# mainboard.net
KiCad netlist of a schematic drawn in EAGLE
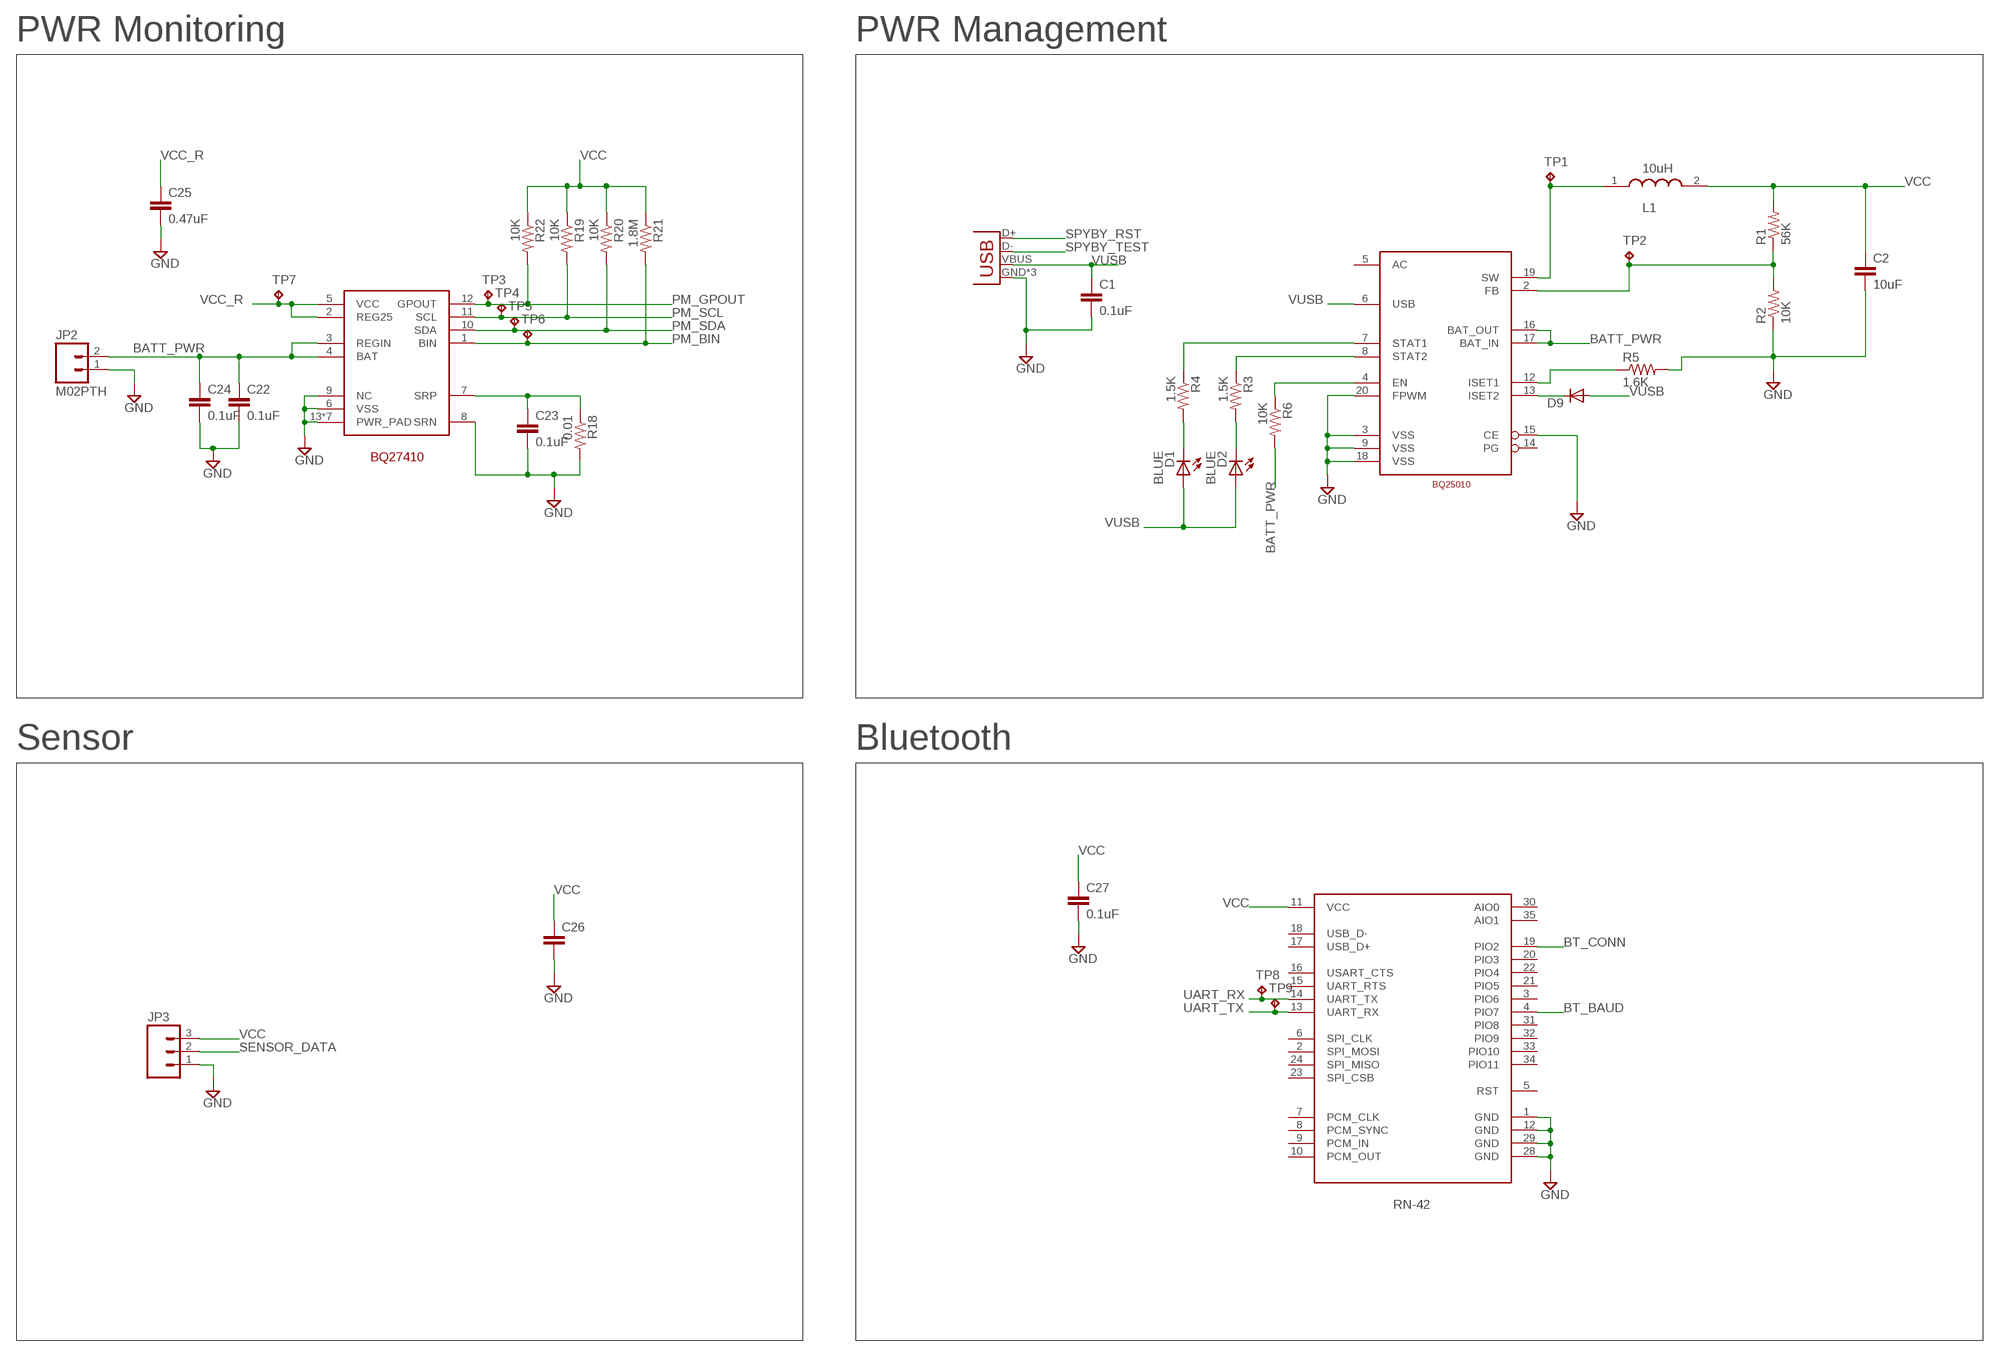
[diagram p0: schematic, sheet 1, part 1 of 2]
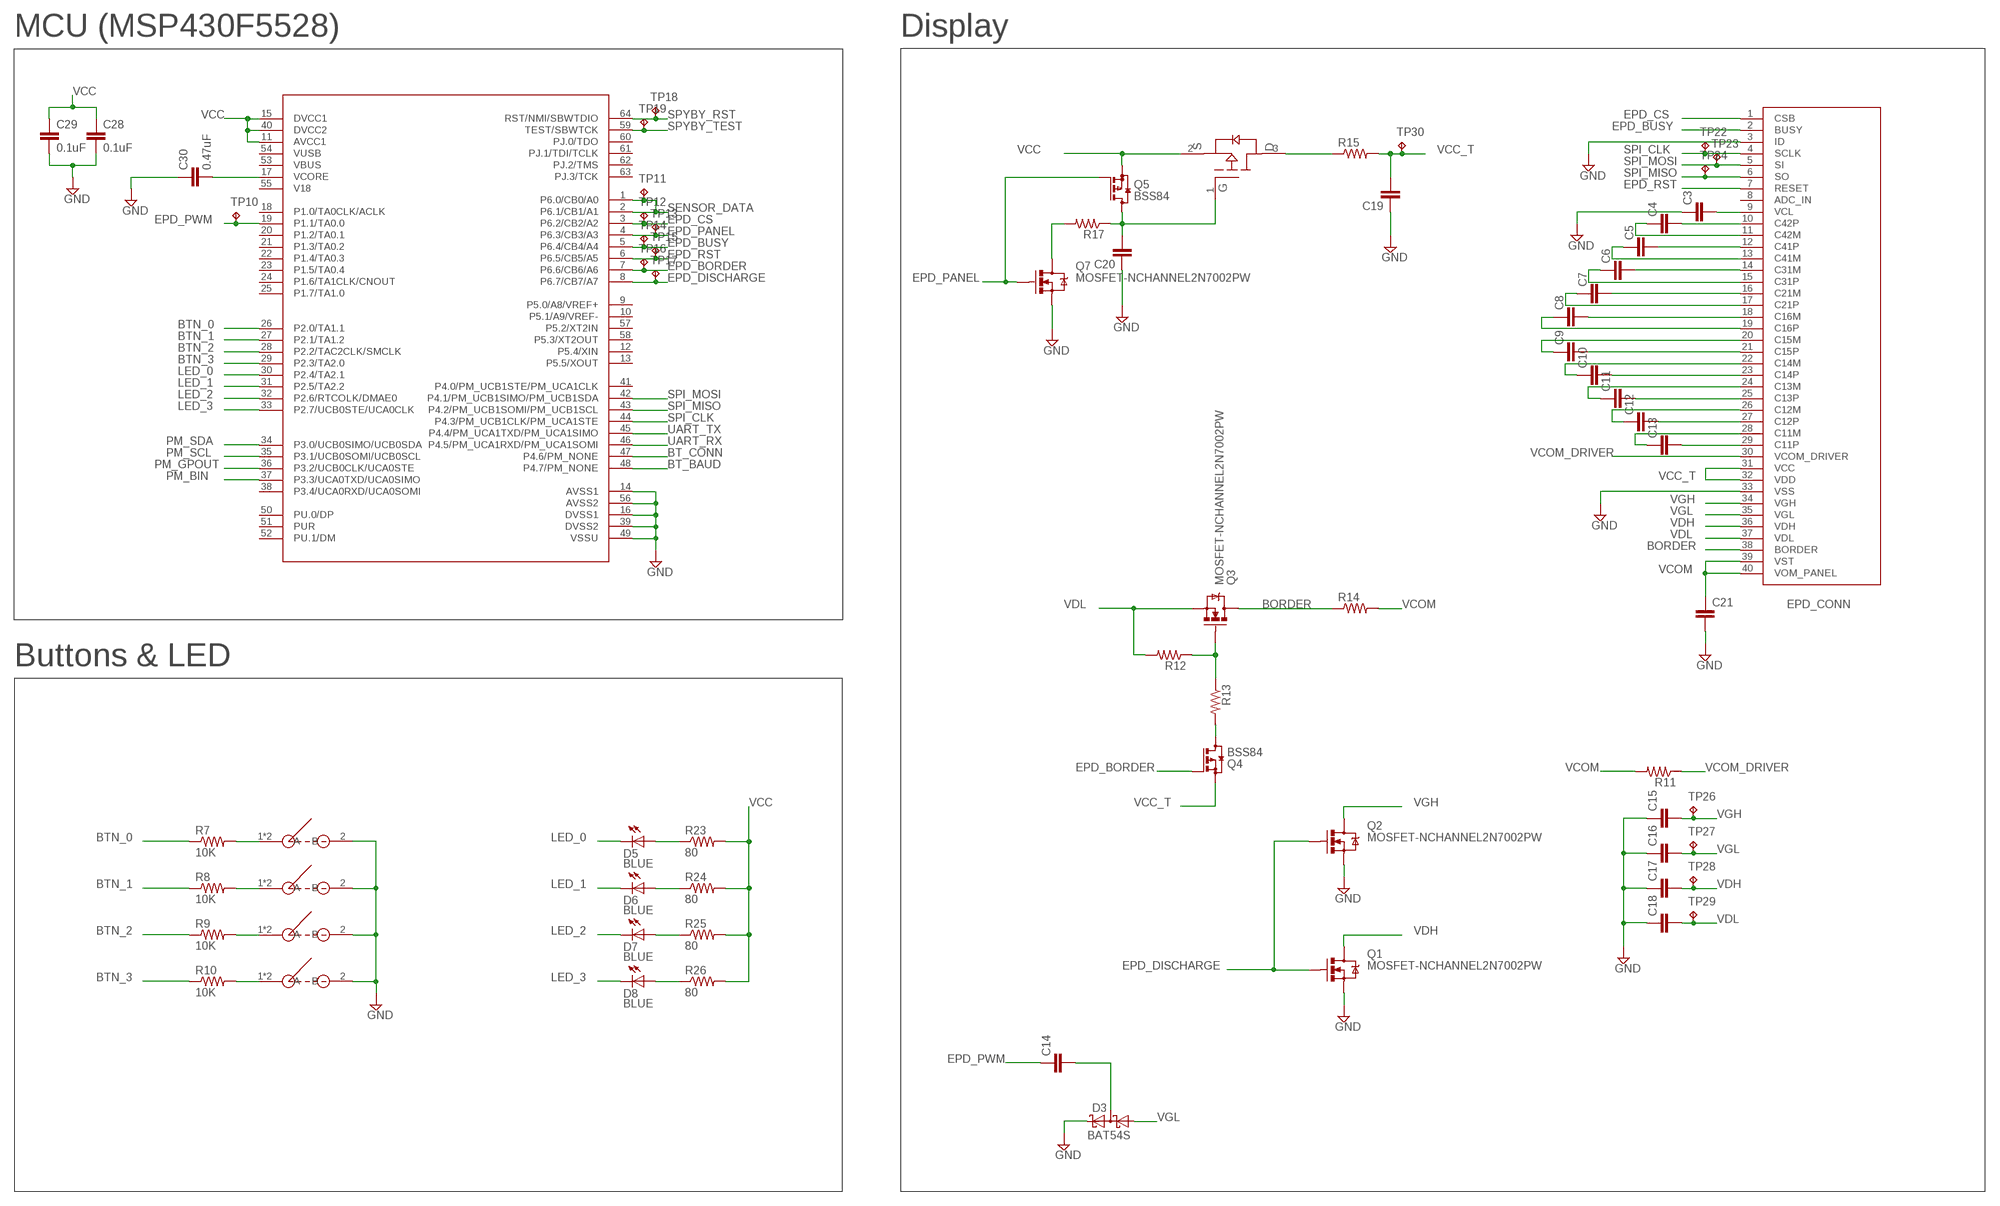
[diagram p1: schematic, sheet 1, part 2 of 2]

(export (version "E")
  (design (tool "Eeschema 10.0.6"))
  (components
    (comp (ref "C1")
      (value "0.1uF")
      (footprint "eagle-import:0402-CAP")
      (libsource (lib "eagle-import") (part "CAP0402-CAP"))
    )
    (comp (ref "C2")
      (value "10uF")
      (footprint "eagle-import:0402-CAP")
      (libsource (lib "eagle-import") (part "CAP0402-CAP"))
    )
    (comp (ref "C3")
      (value "CAP0402-CAP")
      (footprint "eagle-import:0402-CAP")
      (libsource (lib "eagle-import") (part "CAP0402-CAP"))
    )
    (comp (ref "C4")
      (value "CAP0402-CAP")
      (footprint "eagle-import:0402-CAP")
      (libsource (lib "eagle-import") (part "CAP0402-CAP"))
    )
    (comp (ref "C5")
      (value "CAP0402-CAP")
      (footprint "eagle-import:0402-CAP")
      (libsource (lib "eagle-import") (part "CAP0402-CAP"))
    )
    (comp (ref "C6")
      (value "CAP0402-CAP")
      (footprint "eagle-import:0402-CAP")
      (libsource (lib "eagle-import") (part "CAP0402-CAP"))
    )
    (comp (ref "C7")
      (value "CAP0402-CAP")
      (footprint "eagle-import:0402-CAP")
      (libsource (lib "eagle-import") (part "CAP0402-CAP"))
    )
    (comp (ref "C8")
      (value "CAP0402-CAP")
      (footprint "eagle-import:0402-CAP")
      (libsource (lib "eagle-import") (part "CAP0402-CAP"))
    )
    (comp (ref "C9")
      (value "CAP0402-CAP")
      (footprint "eagle-import:0402-CAP")
      (libsource (lib "eagle-import") (part "CAP0402-CAP"))
    )
    (comp (ref "C10")
      (value "CAP0402-CAP")
      (footprint "eagle-import:0402-CAP")
      (libsource (lib "eagle-import") (part "CAP0402-CAP"))
    )
    (comp (ref "C11")
      (value "CAP0402-CAP")
      (footprint "eagle-import:0402-CAP")
      (libsource (lib "eagle-import") (part "CAP0402-CAP"))
    )
    (comp (ref "C12")
      (value "CAP0402-CAP")
      (footprint "eagle-import:0402-CAP")
      (libsource (lib "eagle-import") (part "CAP0402-CAP"))
    )
    (comp (ref "C13")
      (value "CAP0402-CAP")
      (footprint "eagle-import:0402-CAP")
      (libsource (lib "eagle-import") (part "CAP0402-CAP"))
    )
    (comp (ref "C14")
      (value "CAP0402-CAP")
      (footprint "eagle-import:0402-CAP")
      (libsource (lib "eagle-import") (part "CAP0402-CAP"))
    )
    (comp (ref "C15")
      (value "CAP0402-CAP")
      (footprint "eagle-import:0402-CAP")
      (libsource (lib "eagle-import") (part "CAP0402-CAP"))
    )
    (comp (ref "C16")
      (value "CAP0402-CAP")
      (footprint "eagle-import:0402-CAP")
      (libsource (lib "eagle-import") (part "CAP0402-CAP"))
    )
    (comp (ref "C17")
      (value "CAP0402-CAP")
      (footprint "eagle-import:0402-CAP")
      (libsource (lib "eagle-import") (part "CAP0402-CAP"))
    )
    (comp (ref "C18")
      (value "CAP0402-CAP")
      (footprint "eagle-import:0402-CAP")
      (libsource (lib "eagle-import") (part "CAP0402-CAP"))
    )
    (comp (ref "C19")
      (value "CAP0402-CAP")
      (footprint "eagle-import:0402-CAP")
      (libsource (lib "eagle-import") (part "CAP0402-CAP"))
    )
    (comp (ref "C20")
      (value "CAP0402-CAP")
      (footprint "eagle-import:0402-CAP")
      (libsource (lib "eagle-import") (part "CAP0402-CAP"))
    )
    (comp (ref "C21")
      (value "CAP0402-CAP")
      (footprint "eagle-import:0402-CAP")
      (libsource (lib "eagle-import") (part "CAP0402-CAP"))
    )
    (comp (ref "C22")
      (value "0.1uF")
      (footprint "eagle-import:0402-CAP")
      (libsource (lib "eagle-import") (part "CAP0402-CAP"))
    )
    (comp (ref "C23")
      (value "0.1uF")
      (footprint "eagle-import:0402-CAP")
      (libsource (lib "eagle-import") (part "CAP0402-CAP"))
    )
    (comp (ref "C24")
      (value "0.1uF")
      (footprint "eagle-import:0402-CAP")
      (libsource (lib "eagle-import") (part "CAP0402-CAP"))
    )
    (comp (ref "C25")
      (value "0.47uF")
      (footprint "eagle-import:0402-CAP")
      (libsource (lib "eagle-import") (part "CAP0402-CAP"))
    )
    (comp (ref "C26")
      (value "CAP0402-CAP")
      (footprint "eagle-import:0402-CAP")
      (libsource (lib "eagle-import") (part "CAP0402-CAP"))
    )
    (comp (ref "C27")
      (value "0.1uF")
      (footprint "eagle-import:0402-CAP")
      (libsource (lib "eagle-import") (part "CAP0402-CAP"))
    )
    (comp (ref "C28")
      (value "0.1uF")
      (footprint "eagle-import:0402-CAP")
      (libsource (lib "eagle-import") (part "CAP0402-CAP"))
    )
    (comp (ref "C29")
      (value "0.1uF")
      (footprint "eagle-import:0402-CAP")
      (libsource (lib "eagle-import") (part "CAP0402-CAP"))
    )
    (comp (ref "C30")
      (value "0.47uF")
      (footprint "eagle-import:0402-CAP")
      (libsource (lib "eagle-import") (part "CAP0402-CAP"))
    )
    (comp (ref "D1")
      (value "BLUE")
      (footprint "eagle-import:LED-0603")
      (libsource (lib "eagle-import") (part "LED-BLUE0603"))
    )
    (comp (ref "D2")
      (value "BLUE")
      (footprint "eagle-import:LED-0603")
      (libsource (lib "eagle-import") (part "LED-BLUE0603"))
    )
    (comp (ref "D3")
      (value "BAT54S")
      (footprint "eagle-import:SOT23")
      (libsource (lib "eagle-import") (part "BAT54S"))
    )
    (comp (ref "D5")
      (value "BLUE")
      (footprint "eagle-import:LED-0603")
      (libsource (lib "eagle-import") (part "LED-BLUE0603"))
    )
    (comp (ref "D6")
      (value "BLUE")
      (footprint "eagle-import:LED-0603")
      (libsource (lib "eagle-import") (part "LED-BLUE0603"))
    )
    (comp (ref "D7")
      (value "BLUE")
      (footprint "eagle-import:LED-0603")
      (libsource (lib "eagle-import") (part "LED-BLUE0603"))
    )
    (comp (ref "D8")
      (value "BLUE")
      (footprint "eagle-import:LED-0603")
      (libsource (lib "eagle-import") (part "LED-BLUE0603"))
    )
    (comp (ref "D9")
      (value "DIODESOD523")
      (footprint "eagle-import:SOD523")
      (libsource (lib "eagle-import") (part "DIODESOD523"))
    )
    (comp (ref "JP1")
      (value "USB-MICROB")
      (footprint "eagle-import:USB-MICROB")
      (libsource (lib "eagle-import") (part "USB-MICROB"))
    )
    (comp (ref "JP2")
      (value "M02PTH")
      (footprint "eagle-import:1X02")
      (libsource (lib "eagle-import") (part "M02PTH"))
    )
    (comp (ref "JP3")
      (value "M03PTH")
      (footprint "eagle-import:1X03")
      (libsource (lib "eagle-import") (part "M03PTH"))
    )
    (comp (ref "L1")
      (value "10uH")
      (footprint "eagle-import:ASPI_0428S-100M-T")
      (libsource (lib "eagle-import") (part "ASPI-0428S-100M-T"))
    )
    (comp (ref "Q1")
      (value "MOSFET-NCHANNEL2N7002PW")
      (footprint "eagle-import:SOT323")
      (libsource (lib "eagle-import") (part "MOSFET-NCHANNEL2N7002PW"))
    )
    (comp (ref "Q2")
      (value "MOSFET-NCHANNEL2N7002PW")
      (footprint "eagle-import:SOT323")
      (libsource (lib "eagle-import") (part "MOSFET-NCHANNEL2N7002PW"))
    )
    (comp (ref "Q3")
      (value "MOSFET-NCHANNEL2N7002PW")
      (footprint "eagle-import:SOT323")
      (libsource (lib "eagle-import") (part "MOSFET-NCHANNEL2N7002PW"))
    )
    (comp (ref "Q4")
      (value "BSS84")
      (footprint "eagle-import:SOT23")
      (libsource (lib "eagle-import") (part "BSS84"))
    )
    (comp (ref "Q5")
      (value "BSS84")
      (footprint "eagle-import:SOT23")
      (libsource (lib "eagle-import") (part "BSS84"))
    )
    (comp (ref "Q7")
      (value "MOSFET-NCHANNEL2N7002PW")
      (footprint "eagle-import:SOT323")
      (libsource (lib "eagle-import") (part "MOSFET-NCHANNEL2N7002PW"))
    )
    (comp (ref "R1")
      (value "56K")
      (footprint "eagle-import:0402-RES")
      (libsource (lib "eagle-import") (part "RESISTOR0402-RES"))
    )
    (comp (ref "R2")
      (value "10K")
      (footprint "eagle-import:0402-RES")
      (libsource (lib "eagle-import") (part "RESISTOR0402-RES"))
    )
    (comp (ref "R3")
      (value "1.5K")
      (footprint "eagle-import:0402-RES")
      (libsource (lib "eagle-import") (part "RESISTOR0402-RES"))
    )
    (comp (ref "R4")
      (value "1.5K")
      (footprint "eagle-import:0402-RES")
      (libsource (lib "eagle-import") (part "RESISTOR0402-RES"))
    )
    (comp (ref "R5")
      (value "1.6K")
      (footprint "eagle-import:0402-RES")
      (libsource (lib "eagle-import") (part "RESISTOR0402-RES"))
    )
    (comp (ref "R6")
      (value "10K")
      (footprint "eagle-import:0402-RES")
      (libsource (lib "eagle-import") (part "RESISTOR0402-RES"))
    )
    (comp (ref "R7")
      (value "10K")
      (footprint "eagle-import:0402-RES")
      (libsource (lib "eagle-import") (part "RESISTOR0402-RES"))
    )
    (comp (ref "R8")
      (value "10K")
      (footprint "eagle-import:0402-RES")
      (libsource (lib "eagle-import") (part "RESISTOR0402-RES"))
    )
    (comp (ref "R9")
      (value "10K")
      (footprint "eagle-import:0402-RES")
      (libsource (lib "eagle-import") (part "RESISTOR0402-RES"))
    )
    (comp (ref "R10")
      (value "10K")
      (footprint "eagle-import:0402-RES")
      (libsource (lib "eagle-import") (part "RESISTOR0402-RES"))
    )
    (comp (ref "R11")
      (value "RESISTOR0402-RES")
      (footprint "eagle-import:0402-RES")
      (libsource (lib "eagle-import") (part "RESISTOR0402-RES"))
    )
    (comp (ref "R12")
      (value "RESISTOR0402-RES")
      (footprint "eagle-import:0402-RES")
      (libsource (lib "eagle-import") (part "RESISTOR0402-RES"))
    )
    (comp (ref "R13")
      (value "RESISTOR0402-RES")
      (footprint "eagle-import:0402-RES")
      (libsource (lib "eagle-import") (part "RESISTOR0402-RES"))
    )
    (comp (ref "R14")
      (value "RESISTOR0402-RES")
      (footprint "eagle-import:0402-RES")
      (libsource (lib "eagle-import") (part "RESISTOR0402-RES"))
    )
    (comp (ref "R15")
      (value "RESISTOR0402-RES")
      (footprint "eagle-import:0402-RES")
      (libsource (lib "eagle-import") (part "RESISTOR0402-RES"))
    )
    (comp (ref "R17")
      (value "RESISTOR0402-RES")
      (footprint "eagle-import:0402-RES")
      (libsource (lib "eagle-import") (part "RESISTOR0402-RES"))
    )
    (comp (ref "R18")
      (value "0.01")
      (footprint "eagle-import:0402-RES")
      (libsource (lib "eagle-import") (part "RESISTOR0402-RES"))
    )
    (comp (ref "R19")
      (value "10K")
      (footprint "eagle-import:0402-RES")
      (libsource (lib "eagle-import") (part "RESISTOR0402-RES"))
    )
    (comp (ref "R20")
      (value "10K")
      (footprint "eagle-import:0402-RES")
      (libsource (lib "eagle-import") (part "RESISTOR0402-RES"))
    )
    (comp (ref "R21")
      (value "1.8M")
      (footprint "eagle-import:0402-RES")
      (libsource (lib "eagle-import") (part "RESISTOR0402-RES"))
    )
    (comp (ref "R22")
      (value "10K")
      (footprint "eagle-import:0402-RES")
      (libsource (lib "eagle-import") (part "RESISTOR0402-RES"))
    )
    (comp (ref "R23")
      (value "80")
      (footprint "eagle-import:0402-RES")
      (libsource (lib "eagle-import") (part "RESISTOR0402-RES"))
    )
    (comp (ref "R24")
      (value "80")
      (footprint "eagle-import:0402-RES")
      (libsource (lib "eagle-import") (part "RESISTOR0402-RES"))
    )
    (comp (ref "R25")
      (value "80")
      (footprint "eagle-import:0402-RES")
      (libsource (lib "eagle-import") (part "RESISTOR0402-RES"))
    )
    (comp (ref "R26")
      (value "80")
      (footprint "eagle-import:0402-RES")
      (libsource (lib "eagle-import") (part "RESISTOR0402-RES"))
    )
    (comp (ref "TP1")
      (value "TPB1,27")
      (footprint "eagle-import:B1,27")
      (libsource (lib "eagle-import") (part "TPB1,27"))
    )
    (comp (ref "TP2")
      (value "TPB1,27")
      (footprint "eagle-import:B1,27")
      (libsource (lib "eagle-import") (part "TPB1,27"))
    )
    (comp (ref "TP3")
      (value "TPB1,27")
      (footprint "eagle-import:B1,27")
      (libsource (lib "eagle-import") (part "TPB1,27"))
    )
    (comp (ref "TP4")
      (value "TPB1,27")
      (footprint "eagle-import:B1,27")
      (libsource (lib "eagle-import") (part "TPB1,27"))
    )
    (comp (ref "TP5")
      (value "TPB1,27")
      (footprint "eagle-import:B1,27")
      (libsource (lib "eagle-import") (part "TPB1,27"))
    )
    (comp (ref "TP6")
      (value "TPB1,27")
      (footprint "eagle-import:B1,27")
      (libsource (lib "eagle-import") (part "TPB1,27"))
    )
    (comp (ref "TP7")
      (value "TPB1,27")
      (footprint "eagle-import:B1,27")
      (libsource (lib "eagle-import") (part "TPB1,27"))
    )
    (comp (ref "TP8")
      (value "TPB1,27")
      (footprint "eagle-import:B1,27")
      (libsource (lib "eagle-import") (part "TPB1,27"))
    )
    (comp (ref "TP9")
      (value "TPB1,27")
      (footprint "eagle-import:B1,27")
      (libsource (lib "eagle-import") (part "TPB1,27"))
    )
    (comp (ref "TP10")
      (value "TPB1,27")
      (footprint "eagle-import:B1,27")
      (libsource (lib "eagle-import") (part "TPB1,27"))
    )
    (comp (ref "TP11")
      (value "TPB1,27")
      (footprint "eagle-import:B1,27")
      (libsource (lib "eagle-import") (part "TPB1,27"))
    )
    (comp (ref "TP12")
      (value "TPB1,27")
      (footprint "eagle-import:B1,27")
      (libsource (lib "eagle-import") (part "TPB1,27"))
    )
    (comp (ref "TP13")
      (value "TPB1,27")
      (footprint "eagle-import:B1,27")
      (libsource (lib "eagle-import") (part "TPB1,27"))
    )
    (comp (ref "TP14")
      (value "TPB1,27")
      (footprint "eagle-import:B1,27")
      (libsource (lib "eagle-import") (part "TPB1,27"))
    )
    (comp (ref "TP15")
      (value "TPB1,27")
      (footprint "eagle-import:B1,27")
      (libsource (lib "eagle-import") (part "TPB1,27"))
    )
    (comp (ref "TP16")
      (value "TPB1,27")
      (footprint "eagle-import:B1,27")
      (libsource (lib "eagle-import") (part "TPB1,27"))
    )
    (comp (ref "TP17")
      (value "TPB1,27")
      (footprint "eagle-import:B1,27")
      (libsource (lib "eagle-import") (part "TPB1,27"))
    )
    (comp (ref "TP18")
      (value "TPB1,27")
      (footprint "eagle-import:B1,27")
      (libsource (lib "eagle-import") (part "TPB1,27"))
    )
    (comp (ref "TP19")
      (value "TPB1,27")
      (footprint "eagle-import:B1,27")
      (libsource (lib "eagle-import") (part "TPB1,27"))
    )
    (comp (ref "TP22")
      (value "TPB1,27")
      (footprint "eagle-import:B1,27")
      (libsource (lib "eagle-import") (part "TPB1,27"))
    )
    (comp (ref "TP23")
      (value "TPB1,27")
      (footprint "eagle-import:B1,27")
      (libsource (lib "eagle-import") (part "TPB1,27"))
    )
    (comp (ref "TP24")
      (value "TPB1,27")
      (footprint "eagle-import:B1,27")
      (libsource (lib "eagle-import") (part "TPB1,27"))
    )
    (comp (ref "TP26")
      (value "TPB1,27")
      (footprint "eagle-import:B1,27")
      (libsource (lib "eagle-import") (part "TPB1,27"))
    )
    (comp (ref "TP27")
      (value "TPB1,27")
      (footprint "eagle-import:B1,27")
      (libsource (lib "eagle-import") (part "TPB1,27"))
    )
    (comp (ref "TP28")
      (value "TPB1,27")
      (footprint "eagle-import:B1,27")
      (libsource (lib "eagle-import") (part "TPB1,27"))
    )
    (comp (ref "TP29")
      (value "TPB1,27")
      (footprint "eagle-import:B1,27")
      (libsource (lib "eagle-import") (part "TPB1,27"))
    )
    (comp (ref "TP30")
      (value "TPB1,27")
      (footprint "eagle-import:B1,27")
      (libsource (lib "eagle-import") (part "TPB1,27"))
    )
    (comp (ref "U$1")
      (value "MSP430F5528")
      (footprint "eagle-import:VQFN_RGC_64PIN")
      (libsource (lib "eagle-import") (part "MSP430F5528"))
    )
    (comp (ref "U$2")
      (value "RN-42")
      (footprint "eagle-import:RN-42")
      (libsource (lib "eagle-import") (part "RN-42"))
    )
    (comp (ref "U$3")
      (value "BQ25010")
      (footprint "eagle-import:VQFN_RHL_20PIN")
      (libsource (lib "eagle-import") (part "BQ25010"))
    )
    (comp (ref "U$4")
      (value "EVP-AEDB2A")
      (footprint "eagle-import:EVP-AEDB2A")
      (libsource (lib "eagle-import") (part "EVP-AEDB2A"))
    )
    (comp (ref "U$5")
      (value "EVP-AEDB2A")
      (footprint "eagle-import:EVP-AEDB2A")
      (libsource (lib "eagle-import") (part "EVP-AEDB2A"))
    )
    (comp (ref "U$6")
      (value "EVP-AEDB2A")
      (footprint "eagle-import:EVP-AEDB2A")
      (libsource (lib "eagle-import") (part "EVP-AEDB2A"))
    )
    (comp (ref "U$7")
      (value "EVP-AEDB2A")
      (footprint "eagle-import:EVP-AEDB2A")
      (libsource (lib "eagle-import") (part "EVP-AEDB2A"))
    )
    (comp (ref "U$8")
      (value "FH12-40S-0.5SH")
      (footprint "eagle-import:FH12-40S-0.5SH")
      (libsource (lib "eagle-import") (part "FH12-40S-0.5SH"))
    )
    (comp (ref "U$9")
      (value "BQ27410")
      (footprint "eagle-import:SON_DRZ_12PIN")
      (libsource (lib "eagle-import") (part "BQ27410"))
    )
    (comp (ref "U$10")
      (value "DMG2305UX")
      (footprint "eagle-import:SOT23")
      (libsource (lib "eagle-import") (part "DMG2305UX"))
    )
  )
  (nets
    (net (code "1") (name "/BATT_PWR") (class "Default")
      (node (ref "C22") (pin "1") (pinfunction "1_1") (pintype "passive"))
      (node (ref "C24") (pin "1") (pinfunction "1_1") (pintype "passive"))
      (node (ref "JP2") (pin "2") (pinfunction "2_2") (pintype "passive"))
      (node (ref "R6") (pin "2") (pinfunction "2_2") (pintype "passive"))
      (node (ref "U$3") (pin "16") (pinfunction "BAT_OUT_16") (pintype "bidirectional"))
      (node (ref "U$3") (pin "17") (pinfunction "BAT_IN_17") (pintype "bidirectional"))
      (node (ref "U$9") (pin "3") (pinfunction "REGIN_3") (pintype "bidirectional"))
      (node (ref "U$9") (pin "4") (pinfunction "BAT_4") (pintype "bidirectional"))
    )
    (net (code "2") (name "/BORDER") (class "Default")
      (node (ref "Q3") (pin "3") (pinfunction "D_3") (pintype "passive"))
      (node (ref "R14") (pin "1") (pinfunction "1_1") (pintype "passive"))
      (node (ref "U$8") (pin "38") (pinfunction "BORDER_38") (pintype "bidirectional"))
    )
    (net (code "3") (name "/BTN_0") (class "Default")
      (node (ref "R7") (pin "1") (pinfunction "1_1") (pintype "passive"))
      (node (ref "U$1") (pin "26") (pinfunction "P2.0/TA1.1_26") (pintype "bidirectional"))
    )
    (net (code "4") (name "/BTN_1") (class "Default")
      (node (ref "R8") (pin "1") (pinfunction "1_1") (pintype "passive"))
      (node (ref "U$1") (pin "27") (pinfunction "P2.1/TA1.2_27") (pintype "bidirectional"))
    )
    (net (code "5") (name "/BTN_2") (class "Default")
      (node (ref "R9") (pin "1") (pinfunction "1_1") (pintype "passive"))
      (node (ref "U$1") (pin "28") (pinfunction "P2.2/TAC2CLK/SMCLK_28") (pintype "bidirectional"))
    )
    (net (code "6") (name "/BTN_3") (class "Default")
      (node (ref "R10") (pin "1") (pinfunction "1_1") (pintype "passive"))
      (node (ref "U$1") (pin "29") (pinfunction "P2.3/TA2.0_29") (pintype "bidirectional"))
    )
    (net (code "7") (name "/BT_BAUD") (class "Default")
      (node (ref "U$1") (pin "48") (pinfunction "P4.7/PM_NONE_48") (pintype "bidirectional"))
      (node (ref "U$2") (pin "4") (pinfunction "PIO7_4") (pintype "bidirectional"))
    )
    (net (code "8") (name "/BT_CONN") (class "Default")
      (node (ref "U$1") (pin "47") (pinfunction "P4.6/PM_NONE_47") (pintype "bidirectional"))
      (node (ref "U$2") (pin "19") (pinfunction "PIO2_19") (pintype "bidirectional"))
    )
    (net (code "9") (name "/EPD_BORDER") (class "Default")
      (node (ref "Q4") (pin "1") (pinfunction "G_1") (pintype "passive"))
      (node (ref "TP16") (pin "TP") (pinfunction "TP_TP") (pintype "input"))
      (node (ref "U$1") (pin "7") (pinfunction "P6.6/CB6/A6_7") (pintype "bidirectional"))
    )
    (net (code "10") (name "/EPD_BUSY") (class "Default")
      (node (ref "TP14") (pin "TP") (pinfunction "TP_TP") (pintype "input"))
      (node (ref "U$1") (pin "5") (pinfunction "P6.4/CB4/A4_5") (pintype "bidirectional"))
      (node (ref "U$8") (pin "2") (pinfunction "BUSY_2") (pintype "bidirectional"))
    )
    (net (code "11") (name "/EPD_CS") (class "Default")
      (node (ref "TP12") (pin "TP") (pinfunction "TP_TP") (pintype "input"))
      (node (ref "U$1") (pin "3") (pinfunction "P6.2/CB2/A2_3") (pintype "bidirectional"))
      (node (ref "U$8") (pin "1") (pinfunction "CSB_1") (pintype "bidirectional"))
    )
    (net (code "12") (name "/EPD_DISCHARGE") (class "Default")
      (node (ref "Q1") (pin "1") (pinfunction "G_1") (pintype "passive"))
      (node (ref "Q2") (pin "1") (pinfunction "G_1") (pintype "passive"))
      (node (ref "TP17") (pin "TP") (pinfunction "TP_TP") (pintype "input"))
      (node (ref "U$1") (pin "8") (pinfunction "P6.7/CB7/A7_8") (pintype "bidirectional"))
    )
    (net (code "13") (name "/EPD_PANEL") (class "Default")
      (node (ref "Q5") (pin "1") (pinfunction "G_1") (pintype "passive"))
      (node (ref "Q7") (pin "1") (pinfunction "G_1") (pintype "passive"))
      (node (ref "TP13") (pin "TP") (pinfunction "TP_TP") (pintype "input"))
      (node (ref "U$1") (pin "4") (pinfunction "P6.3/CB3/A3_4") (pintype "bidirectional"))
    )
    (net (code "14") (name "/EPD_PWM") (class "Default")
      (node (ref "C14") (pin "1") (pinfunction "1_1") (pintype "passive"))
      (node (ref "TP10") (pin "TP") (pinfunction "TP_TP") (pintype "input"))
      (node (ref "U$1") (pin "19") (pinfunction "P1.1/TA0.0_19") (pintype "bidirectional"))
    )
    (net (code "15") (name "/EPD_RST") (class "Default")
      (node (ref "TP15") (pin "TP") (pinfunction "TP_TP") (pintype "input"))
      (node (ref "U$1") (pin "6") (pinfunction "P6.5/CB5/A5_6") (pintype "bidirectional"))
      (node (ref "U$8") (pin "7") (pinfunction "RESET_7") (pintype "bidirectional"))
    )
    (net (code "16") (name "/LED_0") (class "Default")
      (node (ref "D5") (pin "C") (pinfunction "C_C") (pintype "passive"))
      (node (ref "U$1") (pin "30") (pinfunction "P2.4/TA2.1_30") (pintype "bidirectional"))
    )
    (net (code "17") (name "/LED_1") (class "Default")
      (node (ref "D6") (pin "C") (pinfunction "C_C") (pintype "passive"))
      (node (ref "U$1") (pin "31") (pinfunction "P2.5/TA2.2_31") (pintype "bidirectional"))
    )
    (net (code "18") (name "/LED_2") (class "Default")
      (node (ref "D7") (pin "C") (pinfunction "C_C") (pintype "passive"))
      (node (ref "U$1") (pin "32") (pinfunction "P2.6/RTCOLK/DMAE0_32") (pintype "bidirectional"))
    )
    (net (code "19") (name "/LED_3") (class "Default")
      (node (ref "D8") (pin "C") (pinfunction "C_C") (pintype "passive"))
      (node (ref "U$1") (pin "33") (pinfunction "P2.7/UCB0STE/UCA0CLK_33") (pintype "bidirectional"))
    )
    (net (code "20") (name "/PM_BIN") (class "Default")
      (node (ref "R21") (pin "2") (pinfunction "2_2") (pintype "passive"))
      (node (ref "TP6") (pin "TP") (pinfunction "TP_TP") (pintype "input"))
      (node (ref "U$1") (pin "37") (pinfunction "P3.3/UCA0TXD/UCA0SIMO_37") (pintype "bidirectional"))
      (node (ref "U$9") (pin "1") (pinfunction "BIN_1") (pintype "bidirectional"))
    )
    (net (code "21") (name "/PM_GPOUT") (class "Default")
      (node (ref "R22") (pin "2") (pinfunction "2_2") (pintype "passive"))
      (node (ref "TP3") (pin "TP") (pinfunction "TP_TP") (pintype "input"))
      (node (ref "U$1") (pin "36") (pinfunction "P3.2/UCB0CLK/UCA0STE_36") (pintype "bidirectional"))
      (node (ref "U$9") (pin "12") (pinfunction "GPOUT_12") (pintype "bidirectional"))
    )
    (net (code "22") (name "/PM_SCL") (class "Default")
      (node (ref "R19") (pin "2") (pinfunction "2_2") (pintype "passive"))
      (node (ref "TP4") (pin "TP") (pinfunction "TP_TP") (pintype "input"))
      (node (ref "U$1") (pin "35") (pinfunction "P3.1/UCB0SOMI/UCB0SCL_35") (pintype "bidirectional"))
      (node (ref "U$9") (pin "11") (pinfunction "SCL_11") (pintype "bidirectional"))
    )
    (net (code "23") (name "/PM_SDA") (class "Default")
      (node (ref "R20") (pin "2") (pinfunction "2_2") (pintype "passive"))
      (node (ref "TP5") (pin "TP") (pinfunction "TP_TP") (pintype "input"))
      (node (ref "U$1") (pin "34") (pinfunction "P3.0/UCB0SIMO/UCB0SDA_34") (pintype "bidirectional"))
      (node (ref "U$9") (pin "10") (pinfunction "SDA_10") (pintype "bidirectional"))
    )
    (net (code "24") (name "/SENSOR_DATA") (class "Default")
      (node (ref "JP3") (pin "2") (pinfunction "2_2") (pintype "passive"))
      (node (ref "TP11") (pin "TP") (pinfunction "TP_TP") (pintype "input"))
      (node (ref "U$1") (pin "1") (pinfunction "P6.0/CB0/A0_1") (pintype "bidirectional"))
      (node (ref "U$1") (pin "2") (pinfunction "P6.1/CB1/A1_2") (pintype "bidirectional"))
    )
    (net (code "25") (name "/SPI_CLK") (class "Default")
      (node (ref "TP22") (pin "TP") (pinfunction "TP_TP") (pintype "input"))
      (node (ref "U$1") (pin "44") (pinfunction "P4.3/PM_UCB1CLK/PM_UCA1STE_44") (pintype "bidirectional"))
      (node (ref "U$8") (pin "4") (pinfunction "SCLK_4") (pintype "bidirectional"))
    )
    (net (code "26") (name "/SPI_MISO") (class "Default")
      (node (ref "TP24") (pin "TP") (pinfunction "TP_TP") (pintype "input"))
      (node (ref "U$1") (pin "43") (pinfunction "P4.2/PM_UCB1SOMI/PM_UCB1SCL_43") (pintype "bidirectional"))
      (node (ref "U$8") (pin "6") (pinfunction "SO_6") (pintype "bidirectional"))
    )
    (net (code "27") (name "/SPI_MOSI") (class "Default")
      (node (ref "TP23") (pin "TP") (pinfunction "TP_TP") (pintype "input"))
      (node (ref "U$1") (pin "42") (pinfunction "P4.1/PM_UCB1SIMO/PM_UCB1SDA_42") (pintype "bidirectional"))
      (node (ref "U$8") (pin "5") (pinfunction "SI_5") (pintype "bidirectional"))
    )
    (net (code "28") (name "/SPYBY_RST") (class "Default")
      (node (ref "JP1") (pin "D+") (pinfunction "D+_D+") (pintype "bidirectional"))
      (node (ref "TP18") (pin "TP") (pinfunction "TP_TP") (pintype "input"))
      (node (ref "U$1") (pin "64") (pinfunction "RST/NMI/SBWTDIO_64") (pintype "bidirectional"))
    )
    (net (code "29") (name "/SPYBY_TEST") (class "Default")
      (node (ref "JP1") (pin "D-") (pinfunction "D-_D-") (pintype "bidirectional"))
      (node (ref "TP19") (pin "TP") (pinfunction "TP_TP") (pintype "input"))
      (node (ref "U$1") (pin "59") (pinfunction "TEST/SBWTCK_59") (pintype "bidirectional"))
    )
    (net (code "30") (name "/UART_RX") (class "Default")
      (node (ref "TP8") (pin "TP") (pinfunction "TP_TP") (pintype "input"))
      (node (ref "U$1") (pin "46") (pinfunction "P4.5/PM_UCA1RXD/PM_UCA1SOMI_46") (pintype "bidirectional"))
      (node (ref "U$2") (pin "14") (pinfunction "UART_TX_14") (pintype "bidirectional"))
    )
    (net (code "31") (name "/UART_TX") (class "Default")
      (node (ref "TP9") (pin "TP") (pinfunction "TP_TP") (pintype "input"))
      (node (ref "U$1") (pin "45") (pinfunction "P4.4/PM_UCA1TXD/PM_UCA1SIMO_45") (pintype "bidirectional"))
      (node (ref "U$2") (pin "13") (pinfunction "UART_RX_13") (pintype "bidirectional"))
    )
    (net (code "32") (name "/VCC") (class "Default")
      (node (ref "C2") (pin "1") (pinfunction "1_1") (pintype "passive"))
      (node (ref "C26") (pin "1") (pinfunction "1_1") (pintype "passive"))
      (node (ref "C27") (pin "1") (pinfunction "1_1") (pintype "passive"))
      (node (ref "C28") (pin "1") (pinfunction "1_1") (pintype "passive"))
      (node (ref "C29") (pin "1") (pinfunction "1_1") (pintype "passive"))
      (node (ref "JP3") (pin "3") (pinfunction "3_3") (pintype "passive"))
      (node (ref "L1") (pin "2") (pinfunction "P$2_2") (pintype "bidirectional"))
      (node (ref "Q5") (pin "2") (pinfunction "S_2") (pintype "passive"))
      (node (ref "R1") (pin "2") (pinfunction "2_2") (pintype "passive"))
      (node (ref "R19") (pin "1") (pinfunction "1_1") (pintype "passive"))
      (node (ref "R20") (pin "1") (pinfunction "1_1") (pintype "passive"))
      (node (ref "R21") (pin "1") (pinfunction "1_1") (pintype "passive"))
      (node (ref "R22") (pin "1") (pinfunction "1_1") (pintype "passive"))
      (node (ref "R23") (pin "2") (pinfunction "2_2") (pintype "passive"))
      (node (ref "R24") (pin "2") (pinfunction "2_2") (pintype "passive"))
      (node (ref "R25") (pin "2") (pinfunction "2_2") (pintype "passive"))
      (node (ref "R26") (pin "2") (pinfunction "2_2") (pintype "passive"))
      (node (ref "U$1") (pin "11") (pinfunction "AVCC1_11") (pintype "bidirectional"))
      (node (ref "U$1") (pin "15") (pinfunction "DVCC1_15") (pintype "bidirectional"))
      (node (ref "U$1") (pin "40") (pinfunction "DVCC2_40") (pintype "bidirectional"))
      (node (ref "U$10") (pin "2") (pinfunction "SOURCE_2") (pintype "bidirectional"))
      (node (ref "U$2") (pin "11") (pinfunction "VCC_11") (pintype "bidirectional"))
    )
    (net (code "33") (name "/VCC_R") (class "Default")
      (node (ref "C25") (pin "1") (pinfunction "1_1") (pintype "passive"))
      (node (ref "TP7") (pin "TP") (pinfunction "TP_TP") (pintype "input"))
      (node (ref "U$9") (pin "2") (pinfunction "REG25_2") (pintype "bidirectional"))
      (node (ref "U$9") (pin "5") (pinfunction "VCC_5") (pintype "bidirectional"))
    )
    (net (code "34") (name "/VCC_T") (class "Default")
      (node (ref "C19") (pin "2") (pinfunction "2_2") (pintype "passive"))
      (node (ref "Q4") (pin "2") (pinfunction "S_2") (pintype "passive"))
      (node (ref "R15") (pin "2") (pinfunction "2_2") (pintype "passive"))
      (node (ref "TP30") (pin "TP") (pinfunction "TP_TP") (pintype "input"))
      (node (ref "U$8") (pin "31") (pinfunction "VCC_31") (pintype "bidirectional"))
      (node (ref "U$8") (pin "32") (pinfunction "VDD_32") (pintype "bidirectional"))
    )
    (net (code "35") (name "/VCOM") (class "Default")
      (node (ref "C21") (pin "1") (pinfunction "1_1") (pintype "passive"))
      (node (ref "R11") (pin "2") (pinfunction "2_2") (pintype "passive"))
      (node (ref "R14") (pin "2") (pinfunction "2_2") (pintype "passive"))
      (node (ref "U$8") (pin "39") (pinfunction "VST_39") (pintype "bidirectional"))
      (node (ref "U$8") (pin "40") (pinfunction "VOM_PANEL_40") (pintype "bidirectional"))
    )
    (net (code "36") (name "/VCOM_DRIVER") (class "Default")
      (node (ref "R11") (pin "1") (pinfunction "1_1") (pintype "passive"))
      (node (ref "U$8") (pin "30") (pinfunction "VCOM_DRIVER_30") (pintype "bidirectional"))
    )
    (net (code "37") (name "/VDH") (class "Default")
      (node (ref "C17") (pin "2") (pinfunction "2_2") (pintype "passive"))
      (node (ref "Q1") (pin "3") (pinfunction "D_3") (pintype "passive"))
      (node (ref "TP28") (pin "TP") (pinfunction "TP_TP") (pintype "input"))
      (node (ref "U$8") (pin "36") (pinfunction "VDH_36") (pintype "bidirectional"))
    )
    (net (code "38") (name "/VDL") (class "Default")
      (node (ref "C18") (pin "2") (pinfunction "2_2") (pintype "passive"))
      (node (ref "Q3") (pin "2") (pinfunction "S_2") (pintype "passive"))
      (node (ref "R12") (pin "2") (pinfunction "2_2") (pintype "passive"))
      (node (ref "TP29") (pin "TP") (pinfunction "TP_TP") (pintype "input"))
      (node (ref "U$8") (pin "37") (pinfunction "VDL_37") (pintype "bidirectional"))
    )
    (net (code "39") (name "/VGH") (class "Default")
      (node (ref "C15") (pin "2") (pinfunction "2_2") (pintype "passive"))
      (node (ref "Q2") (pin "3") (pinfunction "D_3") (pintype "passive"))
      (node (ref "TP26") (pin "TP") (pinfunction "TP_TP") (pintype "input"))
      (node (ref "U$8") (pin "34") (pinfunction "VGH_34") (pintype "bidirectional"))
    )
    (net (code "40") (name "/VGL") (class "Default")
      (node (ref "C16") (pin "2") (pinfunction "2_2") (pintype "passive"))
      (node (ref "D3") (pin "1") (pinfunction "A1_1") (pintype "passive"))
      (node (ref "TP27") (pin "TP") (pinfunction "TP_TP") (pintype "input"))
      (node (ref "U$8") (pin "35") (pinfunction "VGL_35") (pintype "bidirectional"))
    )
    (net (code "41") (name "/VUSB") (class "Default")
      (node (ref "C1") (pin "1") (pinfunction "1_1") (pintype "passive"))
      (node (ref "D1") (pin "A") (pinfunction "A_A") (pintype "passive"))
      (node (ref "D2") (pin "A") (pinfunction "A_A") (pintype "passive"))
      (node (ref "D9") (pin "A") (pinfunction "A_A") (pintype "passive"))
      (node (ref "JP1") (pin "VBUS") (pinfunction "VBUS_VBUS") (pintype "bidirectional"))
      (node (ref "U$3") (pin "6") (pinfunction "USB_6") (pintype "bidirectional"))
    )
    (net (code "42") (name "GND") (class "Default")
      (node (ref "C1") (pin "2") (pinfunction "2_2") (pintype "passive"))
      (node (ref "C15") (pin "1") (pinfunction "1_1") (pintype "passive"))
      (node (ref "C16") (pin "1") (pinfunction "1_1") (pintype "passive"))
      (node (ref "C17") (pin "1") (pinfunction "1_1") (pintype "passive"))
      (node (ref "C18") (pin "1") (pinfunction "1_1") (pintype "passive"))
      (node (ref "C19") (pin "1") (pinfunction "1_1") (pintype "passive"))
      (node (ref "C2") (pin "2") (pinfunction "2_2") (pintype "passive"))
      (node (ref "C20") (pin "1") (pinfunction "1_1") (pintype "passive"))
      (node (ref "C21") (pin "2") (pinfunction "2_2") (pintype "passive"))
      (node (ref "C22") (pin "2") (pinfunction "2_2") (pintype "passive"))
      (node (ref "C23") (pin "2") (pinfunction "2_2") (pintype "passive"))
      (node (ref "C24") (pin "2") (pinfunction "2_2") (pintype "passive"))
      (node (ref "C25") (pin "2") (pinfunction "2_2") (pintype "passive"))
      (node (ref "C26") (pin "2") (pinfunction "2_2") (pintype "passive"))
      (node (ref "C27") (pin "2") (pinfunction "2_2") (pintype "passive"))
      (node (ref "C28") (pin "2") (pinfunction "2_2") (pintype "passive"))
      (node (ref "C29") (pin "2") (pinfunction "2_2") (pintype "passive"))
      (node (ref "C3") (pin "1") (pinfunction "1_1") (pintype "passive"))
      (node (ref "C30") (pin "1") (pinfunction "1_1") (pintype "passive"))
      (node (ref "D3") (pin "2") (pinfunction "C2_2") (pintype "passive"))
      (node (ref "JP1") (pin "GND") (pinfunction "GND_GND") (pintype "bidirectional"))
      (node (ref "JP1") (pin "MT1") (pinfunction "GND_MT1") (pintype "bidirectional"))
      (node (ref "JP1") (pin "MT2") (pinfunction "GND_MT2") (pintype "bidirectional"))
      (node (ref "JP2") (pin "1") (pinfunction "1_1") (pintype "passive"))
      (node (ref "JP3") (pin "1") (pinfunction "1_1") (pintype "passive"))
      (node (ref "Q1") (pin "2") (pinfunction "S_2") (pintype "passive"))
      (node (ref "Q2") (pin "2") (pinfunction "S_2") (pintype "passive"))
      (node (ref "Q7") (pin "2") (pinfunction "S_2") (pintype "passive"))
      (node (ref "R18") (pin "2") (pinfunction "2_2") (pintype "passive"))
      (node (ref "R2") (pin "1") (pinfunction "1_1") (pintype "passive"))
      (node (ref "R5") (pin "2") (pinfunction "2_2") (pintype "passive"))
      (node (ref "U$1") (pin "14") (pinfunction "AVSS1_14") (pintype "bidirectional"))
      (node (ref "U$1") (pin "16") (pinfunction "DVSS1_16") (pintype "bidirectional"))
      (node (ref "U$1") (pin "39") (pinfunction "DVSS2_39") (pintype "bidirectional"))
      (node (ref "U$1") (pin "49") (pinfunction "VSSU_49") (pintype "bidirectional"))
      (node (ref "U$1") (pin "56") (pinfunction "AVSS2_56") (pintype "bidirectional"))
      (node (ref "U$2") (pin "1") (pinfunction "GND_1") (pintype "bidirectional"))
      (node (ref "U$2") (pin "12") (pinfunction "GND_12") (pintype "bidirectional"))
      (node (ref "U$2") (pin "28") (pinfunction "GND_28") (pintype "bidirectional"))
      (node (ref "U$2") (pin "29") (pinfunction "GND_29") (pintype "bidirectional"))
      (node (ref "U$3") (pin "15") (pinfunction "CE_15") (pintype "bidirectional"))
      (node (ref "U$3") (pin "18") (pinfunction "VSS_18") (pintype "bidirectional"))
      (node (ref "U$3") (pin "20") (pinfunction "FPWM_20") (pintype "bidirectional"))
      (node (ref "U$3") (pin "3") (pinfunction "VSS_3") (pintype "bidirectional"))
      (node (ref "U$3") (pin "9") (pinfunction "VSS_9") (pintype "bidirectional"))
      (node (ref "U$4") (pin "2") (pinfunction "B_2") (pintype "bidirectional"))
      (node (ref "U$5") (pin "2") (pinfunction "B_2") (pintype "bidirectional"))
      (node (ref "U$6") (pin "2") (pinfunction "B_2") (pintype "bidirectional"))
      (node (ref "U$7") (pin "2") (pinfunction "B_2") (pintype "bidirectional"))
      (node (ref "U$8") (pin "3") (pinfunction "ID_3") (pintype "bidirectional"))
      (node (ref "U$8") (pin "33") (pinfunction "VSS_33") (pintype "bidirectional"))
      (node (ref "U$9") (pin "13") (pinfunction "PWR_PAD_13") (pintype "bidirectional"))
      (node (ref "U$9") (pin "6") (pinfunction "VSS_6") (pintype "bidirectional"))
      (node (ref "U$9") (pin "8") (pinfunction "SRN_8") (pintype "bidirectional"))
      (node (ref "U$9") (pin "9") (pinfunction "NC_9") (pintype "bidirectional"))
      (node (ref "U$9") (pin "P$15") (pinfunction "PWR_PAD_P$15") (pintype "bidirectional"))
      (node (ref "U$9") (pin "P$16") (pinfunction "PWR_PAD_P$16") (pintype "bidirectional"))
      (node (ref "U$9") (pin "P$17") (pinfunction "PWR_PAD_P$17") (pintype "bidirectional"))
      (node (ref "U$9") (pin "P$18") (pinfunction "PWR_PAD_P$18") (pintype "bidirectional"))
      (node (ref "U$9") (pin "P$19") (pinfunction "PWR_PAD_P$19") (pintype "bidirectional"))
      (node (ref "U$9") (pin "P$20") (pinfunction "PWR_PAD_P$20") (pintype "bidirectional"))
    )
    (net (code "43") (name "Net-(D1-PadC)") (class "Default")
      (node (ref "D1") (pin "C") (pinfunction "C_C") (pintype "passive"))
      (node (ref "R4") (pin "2") (pinfunction "2_2") (pintype "passive"))
    )
    (net (code "44") (name "Net-(D2-PadC)") (class "Default")
      (node (ref "D2") (pin "C") (pinfunction "C_C") (pintype "passive"))
      (node (ref "R3") (pin "2") (pinfunction "2_2") (pintype "passive"))
    )
    (net (code "45") (name "Net-(D3-C1A2)") (class "Default")
      (node (ref "C14") (pin "2") (pinfunction "2_2") (pintype "passive"))
      (node (ref "D3") (pin "3") (pinfunction "C1A2_3") (pintype "passive"))
    )
    (net (code "46") (name "Net-(D5-PadA)") (class "Default")
      (node (ref "D5") (pin "A") (pinfunction "A_A") (pintype "passive"))
      (node (ref "R23") (pin "1") (pinfunction "1_1") (pintype "passive"))
    )
    (net (code "47") (name "Net-(D6-PadA)") (class "Default")
      (node (ref "D6") (pin "A") (pinfunction "A_A") (pintype "passive"))
      (node (ref "R24") (pin "1") (pinfunction "1_1") (pintype "passive"))
    )
    (net (code "48") (name "Net-(D7-PadA)") (class "Default")
      (node (ref "D7") (pin "A") (pinfunction "A_A") (pintype "passive"))
      (node (ref "R25") (pin "1") (pinfunction "1_1") (pintype "passive"))
    )
    (net (code "49") (name "Net-(D8-PadA)") (class "Default")
      (node (ref "D8") (pin "A") (pinfunction "A_A") (pintype "passive"))
      (node (ref "R26") (pin "1") (pinfunction "1_1") (pintype "passive"))
    )
    (net (code "50") (name "Net-(L1-P$1)") (class "Default")
      (node (ref "L1") (pin "1") (pinfunction "P$1_1") (pintype "bidirectional"))
      (node (ref "TP1") (pin "TP") (pinfunction "TP_TP") (pintype "input"))
      (node (ref "U$3") (pin "19") (pinfunction "SW_19") (pintype "bidirectional"))
    )
    (net (code "51") (name "Net-(Q3-G)") (class "Default")
      (node (ref "Q3") (pin "1") (pinfunction "G_1") (pintype "passive"))
      (node (ref "R12") (pin "1") (pinfunction "1_1") (pintype "passive"))
      (node (ref "R13") (pin "1") (pinfunction "1_1") (pintype "passive"))
    )
    (net (code "52") (name "Net-(Q4-D)") (class "Default")
      (node (ref "Q4") (pin "3") (pinfunction "D_3") (pintype "passive"))
      (node (ref "R13") (pin "2") (pinfunction "2_2") (pintype "passive"))
    )
    (net (code "53") (name "Net-(Q5-D)") (class "Default")
      (node (ref "C20") (pin "2") (pinfunction "2_2") (pintype "passive"))
      (node (ref "Q5") (pin "3") (pinfunction "D_3") (pintype "passive"))
      (node (ref "R17") (pin "1") (pinfunction "1_1") (pintype "passive"))
      (node (ref "U$10") (pin "1") (pinfunction "GATE_1") (pintype "bidirectional"))
    )
    (net (code "54") (name "Net-(Q7-D)") (class "Default")
      (node (ref "Q7") (pin "3") (pinfunction "D_3") (pintype "passive"))
      (node (ref "R17") (pin "2") (pinfunction "2_2") (pintype "passive"))
    )
    (net (code "55") (name "Net-(R7-Pad2)") (class "Default")
      (node (ref "R7") (pin "2") (pinfunction "2_2") (pintype "passive"))
      (node (ref "U$4") (pin "1") (pinfunction "A_1") (pintype "bidirectional"))
      (node (ref "U$4") (pin "1'") (pinfunction "A_1'") (pintype "bidirectional"))
    )
    (net (code "56") (name "Net-(R8-Pad2)") (class "Default")
      (node (ref "R8") (pin "2") (pinfunction "2_2") (pintype "passive"))
      (node (ref "U$5") (pin "1") (pinfunction "A_1") (pintype "bidirectional"))
      (node (ref "U$5") (pin "1'") (pinfunction "A_1'") (pintype "bidirectional"))
    )
    (net (code "57") (name "Net-(R9-Pad2)") (class "Default")
      (node (ref "R9") (pin "2") (pinfunction "2_2") (pintype "passive"))
      (node (ref "U$6") (pin "1") (pinfunction "A_1") (pintype "bidirectional"))
      (node (ref "U$6") (pin "1'") (pinfunction "A_1'") (pintype "bidirectional"))
    )
    (net (code "58") (name "Net-(R10-Pad2)") (class "Default")
      (node (ref "R10") (pin "2") (pinfunction "2_2") (pintype "passive"))
      (node (ref "U$7") (pin "1") (pinfunction "A_1") (pintype "bidirectional"))
      (node (ref "U$7") (pin "1'") (pinfunction "A_1'") (pintype "bidirectional"))
    )
    (net (code "59") (name "Net-(U$1-VCORE)") (class "Default")
      (node (ref "C30") (pin "2") (pinfunction "2_2") (pintype "passive"))
      (node (ref "U$1") (pin "17") (pinfunction "VCORE_17") (pintype "bidirectional"))
    )
    (net (code "60") (name "Net-(U$3-EN)") (class "Default")
      (node (ref "R6") (pin "1") (pinfunction "1_1") (pintype "passive"))
      (node (ref "U$3") (pin "4") (pinfunction "EN_4") (pintype "bidirectional"))
    )
    (net (code "61") (name "Net-(U$3-FB)") (class "Default")
      (node (ref "R1") (pin "1") (pinfunction "1_1") (pintype "passive"))
      (node (ref "R2") (pin "2") (pinfunction "2_2") (pintype "passive"))
      (node (ref "TP2") (pin "TP") (pinfunction "TP_TP") (pintype "input"))
      (node (ref "U$3") (pin "2") (pinfunction "FB_2") (pintype "bidirectional"))
    )
    (net (code "62") (name "Net-(U$3-ISET1)") (class "Default")
      (node (ref "R5") (pin "1") (pinfunction "1_1") (pintype "passive"))
      (node (ref "U$3") (pin "12") (pinfunction "ISET1_12") (pintype "bidirectional"))
    )
    (net (code "63") (name "Net-(U$3-ISET2)") (class "Default")
      (node (ref "D9") (pin "C") (pinfunction "C_C") (pintype "passive"))
      (node (ref "U$3") (pin "13") (pinfunction "ISET2_13") (pintype "bidirectional"))
    )
    (net (code "64") (name "Net-(U$3-STAT1)") (class "Default")
      (node (ref "R4") (pin "1") (pinfunction "1_1") (pintype "passive"))
      (node (ref "U$3") (pin "7") (pinfunction "STAT1_7") (pintype "bidirectional"))
    )
    (net (code "65") (name "Net-(U$3-STAT2)") (class "Default")
      (node (ref "R3") (pin "1") (pinfunction "1_1") (pintype "passive"))
      (node (ref "U$3") (pin "8") (pinfunction "STAT2_8") (pintype "bidirectional"))
    )
    (net (code "66") (name "Net-(U$8-C11M)") (class "Default")
      (node (ref "C13") (pin "1") (pinfunction "1_1") (pintype "passive"))
      (node (ref "U$8") (pin "28") (pinfunction "C11M_28") (pintype "bidirectional"))
    )
    (net (code "67") (name "Net-(U$8-C11P)") (class "Default")
      (node (ref "C13") (pin "2") (pinfunction "2_2") (pintype "passive"))
      (node (ref "U$8") (pin "29") (pinfunction "C11P_29") (pintype "bidirectional"))
    )
    (net (code "68") (name "Net-(U$8-C12M)") (class "Default")
      (node (ref "C12") (pin "1") (pinfunction "1_1") (pintype "passive"))
      (node (ref "U$8") (pin "26") (pinfunction "C12M_26") (pintype "bidirectional"))
    )
    (net (code "69") (name "Net-(U$8-C12P)") (class "Default")
      (node (ref "C12") (pin "2") (pinfunction "2_2") (pintype "passive"))
      (node (ref "U$8") (pin "27") (pinfunction "C12P_27") (pintype "bidirectional"))
    )
    (net (code "70") (name "Net-(U$8-C13M)") (class "Default")
      (node (ref "C11") (pin "1") (pinfunction "1_1") (pintype "passive"))
      (node (ref "U$8") (pin "24") (pinfunction "C13M_24") (pintype "bidirectional"))
    )
    (net (code "71") (name "Net-(U$8-C13P)") (class "Default")
      (node (ref "C11") (pin "2") (pinfunction "2_2") (pintype "passive"))
      (node (ref "U$8") (pin "25") (pinfunction "C13P_25") (pintype "bidirectional"))
    )
    (net (code "72") (name "Net-(U$8-C14M)") (class "Default")
      (node (ref "C10") (pin "1") (pinfunction "1_1") (pintype "passive"))
      (node (ref "U$8") (pin "22") (pinfunction "C14M_22") (pintype "bidirectional"))
    )
    (net (code "73") (name "Net-(U$8-C14P)") (class "Default")
      (node (ref "C10") (pin "2") (pinfunction "2_2") (pintype "passive"))
      (node (ref "U$8") (pin "23") (pinfunction "C14P_23") (pintype "bidirectional"))
    )
    (net (code "74") (name "Net-(U$8-C15M)") (class "Default")
      (node (ref "C9") (pin "1") (pinfunction "1_1") (pintype "passive"))
      (node (ref "U$8") (pin "20") (pinfunction "C15M_20") (pintype "bidirectional"))
    )
    (net (code "75") (name "Net-(U$8-C15P)") (class "Default")
      (node (ref "C9") (pin "2") (pinfunction "2_2") (pintype "passive"))
      (node (ref "U$8") (pin "21") (pinfunction "C15P_21") (pintype "bidirectional"))
    )
    (net (code "76") (name "Net-(U$8-C16M)") (class "Default")
      (node (ref "C8") (pin "2") (pinfunction "2_2") (pintype "passive"))
      (node (ref "U$8") (pin "18") (pinfunction "C16M_18") (pintype "bidirectional"))
    )
    (net (code "77") (name "Net-(U$8-C16P)") (class "Default")
      (node (ref "C8") (pin "1") (pinfunction "1_1") (pintype "passive"))
      (node (ref "U$8") (pin "19") (pinfunction "C16P_19") (pintype "bidirectional"))
    )
    (net (code "78") (name "Net-(U$8-C21M)") (class "Default")
      (node (ref "C7") (pin "2") (pinfunction "2_2") (pintype "passive"))
      (node (ref "U$8") (pin "16") (pinfunction "C21M_16") (pintype "bidirectional"))
    )
    (net (code "79") (name "Net-(U$8-C21P)") (class "Default")
      (node (ref "C7") (pin "1") (pinfunction "1_1") (pintype "passive"))
      (node (ref "U$8") (pin "17") (pinfunction "C21P_17") (pintype "bidirectional"))
    )
    (net (code "80") (name "Net-(U$8-C31M)") (class "Default")
      (node (ref "C6") (pin "2") (pinfunction "2_2") (pintype "passive"))
      (node (ref "U$8") (pin "14") (pinfunction "C31M_14") (pintype "bidirectional"))
    )
    (net (code "81") (name "Net-(U$8-C31P)") (class "Default")
      (node (ref "C6") (pin "1") (pinfunction "1_1") (pintype "passive"))
      (node (ref "U$8") (pin "15") (pinfunction "C31P_15") (pintype "bidirectional"))
    )
    (net (code "82") (name "Net-(U$8-C41M)") (class "Default")
      (node (ref "C5") (pin "1") (pinfunction "1_1") (pintype "passive"))
      (node (ref "U$8") (pin "13") (pinfunction "C41M_13") (pintype "bidirectional"))
    )
    (net (code "83") (name "Net-(U$8-C41P)") (class "Default")
      (node (ref "C5") (pin "2") (pinfunction "2_2") (pintype "passive"))
      (node (ref "U$8") (pin "12") (pinfunction "C41P_12") (pintype "bidirectional"))
    )
    (net (code "84") (name "Net-(U$8-C42M)") (class "Default")
      (node (ref "C4") (pin "1") (pinfunction "1_1") (pintype "passive"))
      (node (ref "U$8") (pin "11") (pinfunction "C42M_11") (pintype "bidirectional"))
    )
    (net (code "85") (name "Net-(U$8-C42P)") (class "Default")
      (node (ref "C4") (pin "2") (pinfunction "2_2") (pintype "passive"))
      (node (ref "U$8") (pin "10") (pinfunction "C42P_10") (pintype "bidirectional"))
    )
    (net (code "86") (name "Net-(U$8-VCL)") (class "Default")
      (node (ref "C3") (pin "2") (pinfunction "2_2") (pintype "passive"))
      (node (ref "U$8") (pin "9") (pinfunction "VCL_9") (pintype "bidirectional"))
    )
    (net (code "87") (name "Net-(U$9-SRP)") (class "Default")
      (node (ref "C23") (pin "1") (pinfunction "1_1") (pintype "passive"))
      (node (ref "R18") (pin "1") (pinfunction "1_1") (pintype "passive"))
      (node (ref "U$9") (pin "7") (pinfunction "SRP_7") (pintype "bidirectional"))
    )
    (net (code "88") (name "Net-(U$10-DRAIN)") (class "Default")
      (node (ref "R15") (pin "1") (pinfunction "1_1") (pintype "passive"))
      (node (ref "U$10") (pin "3") (pinfunction "DRAIN_3") (pintype "bidirectional"))
    )
    (net (code "89") (name "unconnected-(U$1-P1.0{slash}TA0CLK{slash}ACLK-Pad18)") (class "Default")
      (node (ref "U$1") (pin "18") (pinfunction "P1.0/TA0CLK/ACLK_18") (pintype "bidirectional"))
    )
    (net (code "90") (name "unconnected-(U$1-P1.2{slash}TA0.1-Pad20)") (class "Default")
      (node (ref "U$1") (pin "20") (pinfunction "P1.2/TA0.1_20") (pintype "bidirectional"))
    )
    (net (code "91") (name "unconnected-(U$1-P1.3{slash}TA0.2-Pad21)") (class "Default")
      (node (ref "U$1") (pin "21") (pinfunction "P1.3/TA0.2_21") (pintype "bidirectional"))
    )
    (net (code "92") (name "unconnected-(U$1-P1.4{slash}TA0.3-Pad22)") (class "Default")
      (node (ref "U$1") (pin "22") (pinfunction "P1.4/TA0.3_22") (pintype "bidirectional"))
    )
    (net (code "93") (name "unconnected-(U$1-P1.5{slash}TA0.4-Pad23)") (class "Default")
      (node (ref "U$1") (pin "23") (pinfunction "P1.5/TA0.4_23") (pintype "bidirectional"))
    )
    (net (code "94") (name "unconnected-(U$1-P1.6{slash}TA1CLK{slash}CNOUT-Pad24)") (class "Default")
      (node (ref "U$1") (pin "24") (pinfunction "P1.6/TA1CLK/CNOUT_24") (pintype "bidirectional"))
    )
    (net (code "95") (name "unconnected-(U$1-P1.7{slash}TA1.0-Pad25)") (class "Default")
      (node (ref "U$1") (pin "25") (pinfunction "P1.7/TA1.0_25") (pintype "bidirectional"))
    )
    (net (code "96") (name "unconnected-(U$1-P3.4{slash}UCA0RXD{slash}UCA0SOMI-Pad38)") (class "Default")
      (node (ref "U$1") (pin "38") (pinfunction "P3.4/UCA0RXD/UCA0SOMI_38") (pintype "bidirectional"))
    )
    (net (code "97") (name "unconnected-(U$1-P4.0{slash}PM_UCB1STE{slash}PM_UCA1CLK-Pad41)") (class "Default")
      (node (ref "U$1") (pin "41") (pinfunction "P4.0/PM_UCB1STE/PM_UCA1CLK_41") (pintype "bidirectional"))
    )
    (net (code "98") (name "unconnected-(U$1-P5.0{slash}A8{slash}VREF+-Pad9)") (class "Default")
      (node (ref "U$1") (pin "9") (pinfunction "P5.0/A8/VREF+_9") (pintype "bidirectional"))
    )
    (net (code "99") (name "unconnected-(U$1-P5.1{slash}A9{slash}VREF--Pad10)") (class "Default")
      (node (ref "U$1") (pin "10") (pinfunction "P5.1/A9/VREF-_10") (pintype "bidirectional"))
    )
    (net (code "100") (name "unconnected-(U$1-P5.2{slash}XT2IN-Pad57)") (class "Default")
      (node (ref "U$1") (pin "57") (pinfunction "P5.2/XT2IN_57") (pintype "bidirectional"))
    )
    (net (code "101") (name "unconnected-(U$1-P5.3{slash}XT2OUT-Pad58)") (class "Default")
      (node (ref "U$1") (pin "58") (pinfunction "P5.3/XT2OUT_58") (pintype "bidirectional"))
    )
    (net (code "102") (name "unconnected-(U$1-P5.4{slash}XIN-Pad12)") (class "Default")
      (node (ref "U$1") (pin "12") (pinfunction "P5.4/XIN_12") (pintype "bidirectional"))
    )
    (net (code "103") (name "unconnected-(U$1-P5.5{slash}XOUT-Pad13)") (class "Default")
      (node (ref "U$1") (pin "13") (pinfunction "P5.5/XOUT_13") (pintype "bidirectional"))
    )
    (net (code "104") (name "unconnected-(U$1-PJ.0{slash}TDO-Pad60)") (class "Default")
      (node (ref "U$1") (pin "60") (pinfunction "PJ.0/TDO_60") (pintype "bidirectional"))
    )
    (net (code "105") (name "unconnected-(U$1-PJ.1{slash}TDI{slash}TCLK-Pad61)") (class "Default")
      (node (ref "U$1") (pin "61") (pinfunction "PJ.1/TDI/TCLK_61") (pintype "bidirectional"))
    )
    (net (code "106") (name "unconnected-(U$1-PJ.2{slash}TMS-Pad62)") (class "Default")
      (node (ref "U$1") (pin "62") (pinfunction "PJ.2/TMS_62") (pintype "bidirectional"))
    )
    (net (code "107") (name "unconnected-(U$1-PJ.3{slash}TCK-Pad63)") (class "Default")
      (node (ref "U$1") (pin "63") (pinfunction "PJ.3/TCK_63") (pintype "bidirectional"))
    )
    (net (code "108") (name "unconnected-(U$1-PU.0{slash}DP-Pad50)") (class "Default")
      (node (ref "U$1") (pin "50") (pinfunction "PU.0/DP_50") (pintype "bidirectional"))
    )
    (net (code "109") (name "unconnected-(U$1-PU.1{slash}DM-Pad52)") (class "Default")
      (node (ref "U$1") (pin "52") (pinfunction "PU.1/DM_52") (pintype "bidirectional"))
    )
    (net (code "110") (name "unconnected-(U$1-PUR-Pad51)") (class "Default")
      (node (ref "U$1") (pin "51") (pinfunction "PUR_51") (pintype "bidirectional"))
    )
    (net (code "111") (name "unconnected-(U$1-V18-Pad55)") (class "Default")
      (node (ref "U$1") (pin "55") (pinfunction "V18_55") (pintype "bidirectional"))
    )
    (net (code "112") (name "unconnected-(U$1-VBUS-Pad53)") (class "Default")
      (node (ref "U$1") (pin "53") (pinfunction "VBUS_53") (pintype "bidirectional"))
    )
    (net (code "113") (name "unconnected-(U$1-VUSB-Pad54)") (class "Default")
      (node (ref "U$1") (pin "54") (pinfunction "VUSB_54") (pintype "bidirectional"))
    )
    (net (code "114") (name "unconnected-(U$2-AIO0-Pad30)") (class "Default")
      (node (ref "U$2") (pin "30") (pinfunction "AIO0_30") (pintype "bidirectional"))
    )
    (net (code "115") (name "unconnected-(U$2-AIO1-Pad35)") (class "Default")
      (node (ref "U$2") (pin "35") (pinfunction "AIO1_35") (pintype "bidirectional"))
    )
    (net (code "116") (name "unconnected-(U$2-PCM_CLK-Pad7)") (class "Default")
      (node (ref "U$2") (pin "7") (pinfunction "PCM_CLK_7") (pintype "bidirectional"))
    )
    (net (code "117") (name "unconnected-(U$2-PCM_IN-Pad9)") (class "Default")
      (node (ref "U$2") (pin "9") (pinfunction "PCM_IN_9") (pintype "bidirectional"))
    )
    (net (code "118") (name "unconnected-(U$2-PCM_OUT-Pad10)") (class "Default")
      (node (ref "U$2") (pin "10") (pinfunction "PCM_OUT_10") (pintype "bidirectional"))
    )
    (net (code "119") (name "unconnected-(U$2-PCM_SYNC-Pad8)") (class "Default")
      (node (ref "U$2") (pin "8") (pinfunction "PCM_SYNC_8") (pintype "bidirectional"))
    )
    (net (code "120") (name "unconnected-(U$2-PIO3-Pad20)") (class "Default")
      (node (ref "U$2") (pin "20") (pinfunction "PIO3_20") (pintype "bidirectional"))
    )
    (net (code "121") (name "unconnected-(U$2-PIO4-Pad22)") (class "Default")
      (node (ref "U$2") (pin "22") (pinfunction "PIO4_22") (pintype "bidirectional"))
    )
    (net (code "122") (name "unconnected-(U$2-PIO5-Pad21)") (class "Default")
      (node (ref "U$2") (pin "21") (pinfunction "PIO5_21") (pintype "bidirectional"))
    )
    (net (code "123") (name "unconnected-(U$2-PIO6-Pad3)") (class "Default")
      (node (ref "U$2") (pin "3") (pinfunction "PIO6_3") (pintype "bidirectional"))
    )
    (net (code "124") (name "unconnected-(U$2-PIO8-Pad31)") (class "Default")
      (node (ref "U$2") (pin "31") (pinfunction "PIO8_31") (pintype "bidirectional"))
    )
    (net (code "125") (name "unconnected-(U$2-PIO9-Pad32)") (class "Default")
      (node (ref "U$2") (pin "32") (pinfunction "PIO9_32") (pintype "bidirectional"))
    )
    (net (code "126") (name "unconnected-(U$2-PIO10-Pad33)") (class "Default")
      (node (ref "U$2") (pin "33") (pinfunction "PIO10_33") (pintype "bidirectional"))
    )
    (net (code "127") (name "unconnected-(U$2-PIO11-Pad34)") (class "Default")
      (node (ref "U$2") (pin "34") (pinfunction "PIO11_34") (pintype "bidirectional"))
    )
    (net (code "128") (name "unconnected-(U$2-RST-Pad5)") (class "Default")
      (node (ref "U$2") (pin "5") (pinfunction "RST_5") (pintype "bidirectional"))
    )
    (net (code "129") (name "unconnected-(U$2-SPI_CLK-Pad6)") (class "Default")
      (node (ref "U$2") (pin "6") (pinfunction "SPI_CLK_6") (pintype "bidirectional"))
    )
    (net (code "130") (name "unconnected-(U$2-SPI_CSB-Pad23)") (class "Default")
      (node (ref "U$2") (pin "23") (pinfunction "SPI_CSB_23") (pintype "bidirectional"))
    )
    (net (code "131") (name "unconnected-(U$2-SPI_MISO-Pad24)") (class "Default")
      (node (ref "U$2") (pin "24") (pinfunction "SPI_MISO_24") (pintype "bidirectional"))
    )
    (net (code "132") (name "unconnected-(U$2-SPI_MOSI-Pad2)") (class "Default")
      (node (ref "U$2") (pin "2") (pinfunction "SPI_MOSI_2") (pintype "bidirectional"))
    )
    (net (code "133") (name "unconnected-(U$2-UART_RTS-Pad15)") (class "Default")
      (node (ref "U$2") (pin "15") (pinfunction "UART_RTS_15") (pintype "bidirectional"))
    )
    (net (code "134") (name "unconnected-(U$2-USART_CTS-Pad16)") (class "Default")
      (node (ref "U$2") (pin "16") (pinfunction "USART_CTS_16") (pintype "bidirectional"))
    )
    (net (code "135") (name "unconnected-(U$2-USB_D+-Pad17)") (class "Default")
      (node (ref "U$2") (pin "17") (pinfunction "USB_D+_17") (pintype "bidirectional"))
    )
    (net (code "136") (name "unconnected-(U$2-USB_D--Pad18)") (class "Default")
      (node (ref "U$2") (pin "18") (pinfunction "USB_D-_18") (pintype "bidirectional"))
    )
    (net (code "137") (name "unconnected-(U$3-AC-Pad5)") (class "Default")
      (node (ref "U$3") (pin "5") (pinfunction "AC_5") (pintype "bidirectional"))
    )
    (net (code "138") (name "unconnected-(U$3-PG-Pad14)") (class "Default")
      (node (ref "U$3") (pin "14") (pinfunction "PG_14") (pintype "bidirectional"))
    )
    (net (code "139") (name "unconnected-(U$8-ADC_IN-Pad8)") (class "Default")
      (node (ref "U$8") (pin "8") (pinfunction "ADC_IN_8") (pintype "bidirectional"))
    )
  )
)
